# overall.net
KiCad netlist of a schematic drawn in Altium Designer
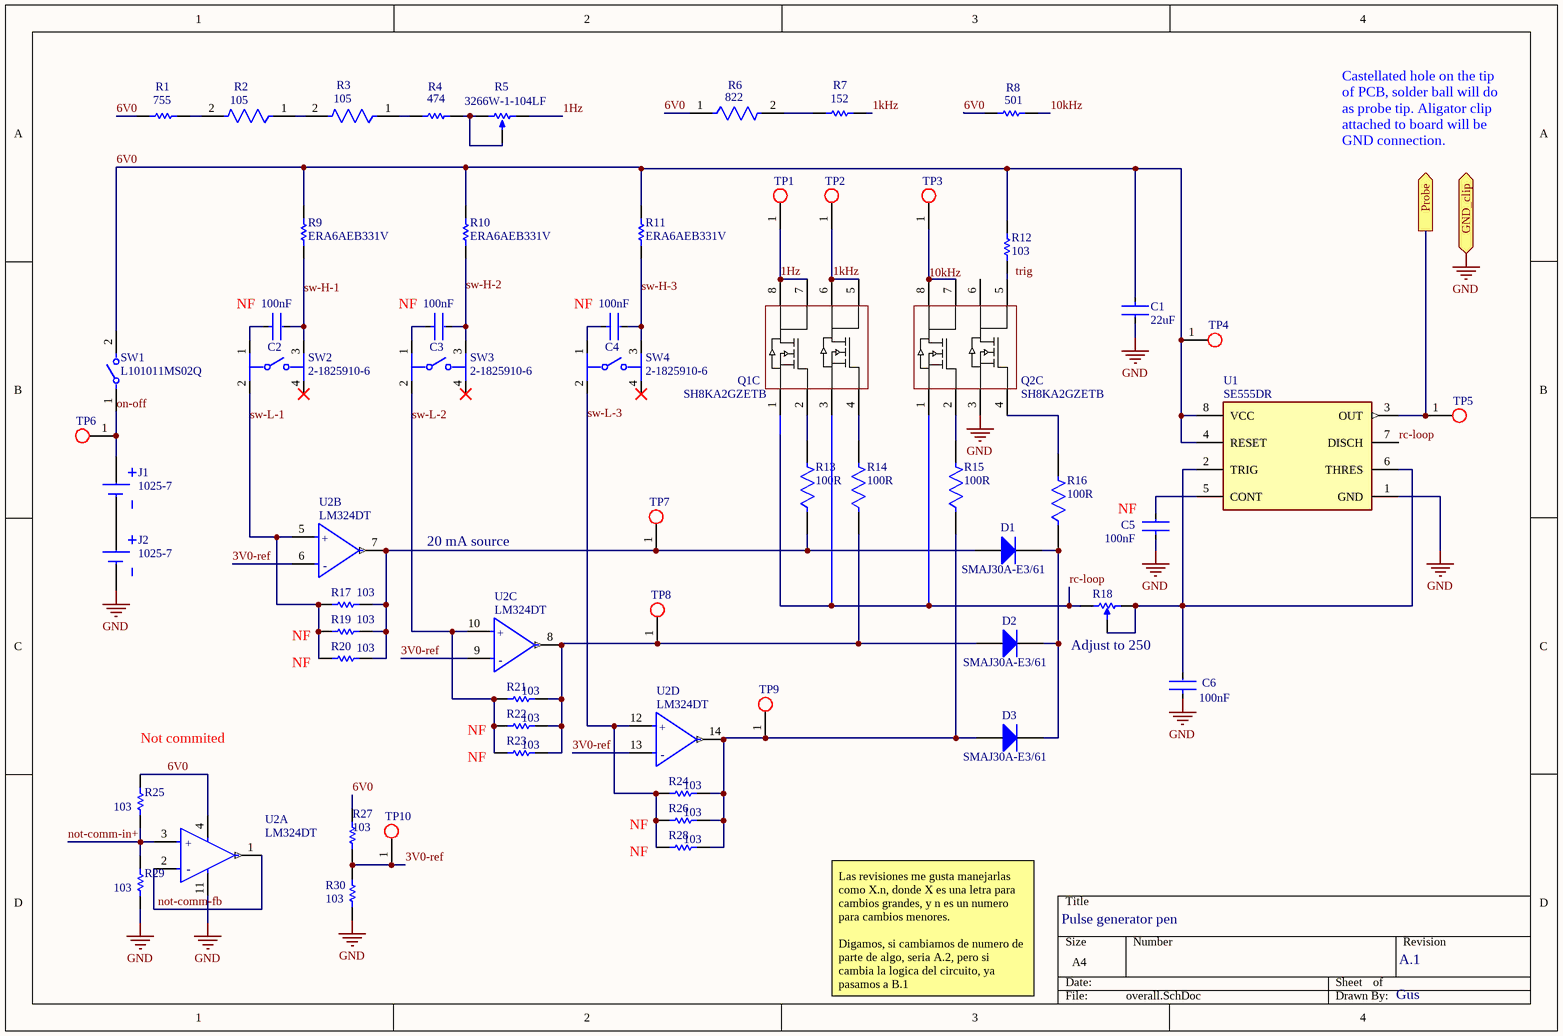
[diagram p0: overall.SchDoc]

(export (version "E")
  (design (tool "Eeschema 10.0.6"))
  (components
    (comp (ref "C1")
      (value "C2012X5R1V226M125AC")
      (footprint "FP-C2012-125-0_2-IPC_A")
      (description "Multilayer Ceramic Capacitors 22μF ±20% 35V X5R SMD 0805")
      (fields (field (name "TOLERANCE") "20%") (field (name "CAPACITANCE") "22uF"))
      (libsource (lib "Altium Content Vault") (part "b4654b650e69147ec39a6b967a45e02"))
    )
    (comp (ref "C2")
      (value "CL21B104KBCNNNC")
      (footprint "FP-CL21-IPC_A")
      (description "CL21 Series 0805 100nF 50V ±10% Tolerance X7R Multilayer Ceramic Chip Capacitor")
      (fields
        (field (name "TOLERANCE") "10%")
        (field (name "CAPACITANCE") "100nF")
        (field (name "VOLTAGE") "50V")
      )
      (libsource (lib "Altium Content Vault") (part "b4654b650e69147ec39a6b967a45e02"))
    )
    (comp (ref "C3")
      (value "CL21B104KBCNNNC")
      (footprint "FP-CL21-IPC_A")
      (description "CL21 Series 0805 100nF 50V ±10% Tolerance X7R Multilayer Ceramic Chip Capacitor")
      (fields
        (field (name "TOLERANCE") "10%")
        (field (name "CAPACITANCE") "100nF")
        (field (name "VOLTAGE") "50V")
      )
      (libsource (lib "Altium Content Vault") (part "b4654b650e69147ec39a6b967a45e02"))
    )
    (comp (ref "C4")
      (value "CL21B104KBCNNNC")
      (footprint "FP-CL21-IPC_A")
      (description "CL21 Series 0805 100nF 50V ±10% Tolerance X7R Multilayer Ceramic Chip Capacitor")
      (fields
        (field (name "TOLERANCE") "10%")
        (field (name "CAPACITANCE") "100nF")
        (field (name "VOLTAGE") "50V")
      )
      (libsource (lib "Altium Content Vault") (part "b4654b650e69147ec39a6b967a45e02"))
    )
    (comp (ref "C5")
      (value "CL21B104KBCNNNC")
      (footprint "FP-CL21-IPC_A")
      (description "CL21 Series 0805 100nF 50V ±10% Tolerance X7R Multilayer Ceramic Chip Capacitor")
      (fields
        (field (name "TOLERANCE") "10%")
        (field (name "CAPACITANCE") "100nF")
        (field (name "VOLTAGE") "50V")
      )
      (libsource (lib "Altium Content Vault") (part "b4654b650e69147ec39a6b967a45e02"))
    )
    (comp (ref "C6")
      (value "CL21B104KBCNNNC")
      (footprint "FP-CL21-IPC_A")
      (description "CL21 Series 0805 100nF 50V ±10% Tolerance X7R Multilayer Ceramic Chip Capacitor")
      (fields
        (field (name "TOLERANCE") "10%")
        (field (name "CAPACITANCE") "100nF")
        (field (name "VOLTAGE") "50V")
      )
      (libsource (lib "Altium Content Vault") (part "b4654b650e69147ec39a6b967a45e02"))
    )
    (comp (ref "D1")
      (value "SMAJ30A-E3/61")
      (footprint "VISH-DO-214AC-2_N")
      (fields (field (name "MANUFACTURER") "Vishay Semiconductor"))
      (libsource (lib "Altium Content Vault") (part "VISH-K1A2-2"))
    )
    (comp (ref "D2")
      (value "SMAJ30A-E3/61")
      (footprint "VISH-DO-214AC-2_N")
      (fields (field (name "MANUFACTURER") "Vishay Semiconductor"))
      (libsource (lib "Altium Content Vault") (part "VISH-K1A2-2"))
    )
    (comp (ref "D3")
      (value "SMAJ30A-E3/61")
      (footprint "VISH-DO-214AC-2_N")
      (fields (field (name "MANUFACTURER") "Vishay Semiconductor"))
      (libsource (lib "Altium Content Vault") (part "VISH-K1A2-2"))
    )
    (comp (ref "J1")
      (value "1025-7")
      (footprint "KEYSTONE-1025-7-2_V")
      (description "Holder for 2477 or 2430 Cells P/N 1025-7, Body 27.762 x 30.963 mm, THM")
      (fields (field (name "MANUFACTURER") "Keystone"))
      (libsource (lib "Altium Content Vault") (part "KEYSTONE-1025-7-2"))
    )
    (comp (ref "J2")
      (value "1025-7")
      (footprint "KEYSTONE-1025-7-2_V")
      (description "Holder for 2477 or 2430 Cells P/N 1025-7, Body 27.762 x 30.963 mm, THM")
      (fields (field (name "MANUFACTURER") "Keystone"))
      (libsource (lib "Altium Content Vault") (part "KEYSTONE-1025-7-2"))
    )
    (comp (ref "Q1")
      (value "SH8KA2GZETB")
      (footprint "SOIC127P600X175-8N")
      (libsource (lib "Cetys University") (part "SH8KA2GZETB"))
    )
    (comp (ref "Q2")
      (value "SH8KA2GZETB")
      (footprint "SOIC127P600X175-8N")
      (libsource (lib "Cetys University") (part "SH8KA2GZETB"))
    )
    (comp (ref "R1")
      (value "CRCW08057M50JNEA")
      (footprint "RESC2013X50X30LL20T20")
      (fields (field (name "MANUFACTURER") "Vishay Dale") (field (name "RESISTANCE") "755"))
      (libsource (lib "Altium Content Vault") (part "RES"))
    )
    (comp (ref "R2")
      (value "ERJ-6ENF1004V")
      (footprint "FP-ERJ6EN-IPC_A")
      (description "RES SMD 1M OHM 1% 1/8W 0805")
      (fields (field (name "RESISTANCE") "105") (field (name "TOLERANCE") "1%"))
      (libsource (lib "") (part "1029c3af85768c4190bb7ad29bc67b5_1"))
    )
    (comp (ref "R3")
      (value "ERJ-6ENF1004V")
      (footprint "FP-ERJ6EN-IPC_A")
      (description "RES SMD 1M OHM 1% 1/8W 0805")
      (fields (field (name "RESISTANCE") "105") (field (name "TOLERANCE") "1%"))
      (libsource (lib "") (part "1029c3af85768c4190bb7ad29bc67b5_1"))
    )
    (comp (ref "R4")
      (value "ERJ6ENF4703V")
      (footprint "RESC2013X70X40ML20T20")
      (fields (field (name "MANUFACTURER") "Panasonic") (field (name "RESISTANCE") "474"))
      (libsource (lib "Altium Content Vault") (part "RES"))
    )
    (comp (ref "R5")
      (value "3266W-1-104LF")
      (footprint "BOUR-3266W-3_V")
      (description "Square Trimpot Trimming Potentiometer, 100 KOhm, 0.25 W, -55 to 125 degC, 3-Pin THD, RoHS, Tube")
      (fields (field (name "TOLERANCE") "+/-10%") (field (name "MANUFACTURER") "Bourns"))
      (libsource (lib "Altium Content Vault") (part "BOUR-POT-3"))
    )
    (comp (ref "R6")
      (value "RC2012J822CS")
      (footprint "FP-RC2012-IPC_A")
      (description "Res Thick Film 0805 8.2kΩ 5% 0.125W ±100ppm/°C Molded SMD T/R")
      (fields (field (name "RESISTANCE") "822") (field (name "TOLERANCE") "5%"))
      (libsource (lib "") (part "1029c3af85768c4190bb7ad29bc67b5_1"))
    )
    (comp (ref "R7")
      (value "RC0805FR-071K5L")
      (footprint "RESC2013X60X35LL10T20")
      (description "RES 1.50K OHM 1/8W 1% 0805 SMD")
      (fields (field (name "MANUFACTURER") "Yageo") (field (name "RESISTANCE") "152"))
      (libsource (lib "") (part "RES-2_1"))
    )
    (comp (ref "R8")
      (value "WSLP0805R0500FEA")
      (footprint "RESC2013X58X38LL25T25")
      (fields (field (name "MANUFACTURER") "Vishay Dale") (field (name "RESISTANCE") "501"))
      (libsource (lib "Altium Content Vault") (part "RES"))
    )
    (comp (ref "R9")
      (value "ERA6AEB331V")
      (footprint "RESC2013X60X40LL20T25")
      (fields (field (name "MANUFACTURER") "Panasonic"))
      (libsource (lib "Altium Content Vault") (part "RES"))
    )
    (comp (ref "R10")
      (value "ERA6AEB331V")
      (footprint "RESC2013X60X40LL20T25")
      (fields (field (name "MANUFACTURER") "Panasonic"))
      (libsource (lib "Altium Content Vault") (part "RES"))
    )
    (comp (ref "R11")
      (value "ERA6AEB331V")
      (footprint "RESC2013X60X40LL20T25")
      (fields (field (name "MANUFACTURER") "Panasonic"))
      (libsource (lib "Altium Content Vault") (part "RES"))
    )
    (comp (ref "R12")
      (value "RC0805FR-0710KL")
      (footprint "RESC2013X60X35NL10T20")
      (description "Chip Resistor, 10 KOhm, +/- 1%, 0.125 W, -55 to 155 degC, 0805 (2012 Metric), RoHS, Tape and Reel")
      (fields (field (name "MANUFACTURER") "Yageo") (field (name "RESISTANCE") "103"))
      (libsource (lib "Altium Content Vault") (part "RES-2"))
    )
    (comp (ref "R13")
      (value "CRCW0805100RFKEAHP")
      (footprint "FP-CRCW0805-HPe3-IPC_A")
      (description "RES Thick Film, 100Ω, 1%, 0.5W, 100ppm/°C, 0805")
      (fields (field (name "TOLERANCE") "1%") (field (name "RESISTANCE") "100R"))
      (libsource (lib "Altium Content Vault") (part "1029c3af85768c4190bb7ad29bc67b5"))
    )
    (comp (ref "R14")
      (value "CRCW0805100RFKEAHP")
      (footprint "FP-CRCW0805-HPe3-IPC_A")
      (description "RES Thick Film, 100Ω, 1%, 0.5W, 100ppm/°C, 0805")
      (fields (field (name "TOLERANCE") "1%") (field (name "RESISTANCE") "100R"))
      (libsource (lib "Altium Content Vault") (part "1029c3af85768c4190bb7ad29bc67b5"))
    )
    (comp (ref "R15")
      (value "CRCW0805100RFKEAHP")
      (footprint "FP-CRCW0805-HPe3-IPC_A")
      (description "RES Thick Film, 100Ω, 1%, 0.5W, 100ppm/°C, 0805")
      (fields (field (name "TOLERANCE") "1%") (field (name "RESISTANCE") "100R"))
      (libsource (lib "Altium Content Vault") (part "1029c3af85768c4190bb7ad29bc67b5"))
    )
    (comp (ref "R16")
      (value "CRCW0805100RFKEAHP")
      (footprint "FP-CRCW0805-HPe3-IPC_A")
      (description "RES Thick Film, 100Ω, 1%, 0.5W, 100ppm/°C, 0805")
      (fields (field (name "TOLERANCE") "1%") (field (name "RESISTANCE") "100R"))
      (libsource (lib "Altium Content Vault") (part "1029c3af85768c4190bb7ad29bc67b5"))
    )
    (comp (ref "R17")
      (value "RC0805FR-0710KL")
      (footprint "RESC2013X60X35NL10T20")
      (description "Chip Resistor, 10 KOhm, +/- 1%, 0.125 W, -55 to 155 degC, 0805 (2012 Metric), RoHS, Tape and Reel")
      (fields (field (name "MANUFACTURER") "Yageo") (field (name "RESISTANCE") "103"))
      (libsource (lib "Altium Content Vault") (part "RES-2"))
    )
    (comp (ref "R18")
      (value "3296W-1-102LF")
      (footprint "BOUR-3296W-1-3")
      (description "Square Trimpot(R) Trimming Potentiometer, 1000 Ohm, -55 to 125 degC, 3-Pin THD, RoHS, Tube")
      (fields (field (name "TOLERANCE") "1%"))
      (libsource (lib "Altium Content Vault") (part "RES-ADJ-3"))
    )
    (comp (ref "R19")
      (value "RC0805FR-0710KL")
      (footprint "RESC2013X60X35NL10T20")
      (description "Chip Resistor, 10 KOhm, +/- 1%, 0.125 W, -55 to 155 degC, 0805 (2012 Metric), RoHS, Tape and Reel")
      (fields (field (name "MANUFACTURER") "Yageo") (field (name "RESISTANCE") "103"))
      (libsource (lib "Altium Content Vault") (part "RES-2"))
    )
    (comp (ref "R20")
      (value "RC0805FR-0710KL")
      (footprint "RESC2013X60X35NL10T20")
      (description "Chip Resistor, 10 KOhm, +/- 1%, 0.125 W, -55 to 155 degC, 0805 (2012 Metric), RoHS, Tape and Reel")
      (fields (field (name "MANUFACTURER") "Yageo") (field (name "RESISTANCE") "103"))
      (libsource (lib "Altium Content Vault") (part "RES-2"))
    )
    (comp (ref "R21")
      (value "RC0805FR-0710KL")
      (footprint "RESC2013X60X35NL10T20")
      (description "Chip Resistor, 10 KOhm, +/- 1%, 0.125 W, -55 to 155 degC, 0805 (2012 Metric), RoHS, Tape and Reel")
      (fields (field (name "MANUFACTURER") "Yageo") (field (name "RESISTANCE") "103"))
      (libsource (lib "Altium Content Vault") (part "RES-2"))
    )
    (comp (ref "R22")
      (value "RC0805FR-0710KL")
      (footprint "RESC2013X60X35NL10T20")
      (description "Chip Resistor, 10 KOhm, +/- 1%, 0.125 W, -55 to 155 degC, 0805 (2012 Metric), RoHS, Tape and Reel")
      (fields (field (name "MANUFACTURER") "Yageo") (field (name "RESISTANCE") "103"))
      (libsource (lib "Altium Content Vault") (part "RES-2"))
    )
    (comp (ref "R23")
      (value "RC0805FR-0710KL")
      (footprint "RESC2013X60X35NL10T20")
      (description "Chip Resistor, 10 KOhm, +/- 1%, 0.125 W, -55 to 155 degC, 0805 (2012 Metric), RoHS, Tape and Reel")
      (fields (field (name "MANUFACTURER") "Yageo") (field (name "RESISTANCE") "103"))
      (libsource (lib "Altium Content Vault") (part "RES-2"))
    )
    (comp (ref "R24")
      (value "RC0805FR-0710KL")
      (footprint "RESC2013X60X35NL10T20")
      (description "Chip Resistor, 10 KOhm, +/- 1%, 0.125 W, -55 to 155 degC, 0805 (2012 Metric), RoHS, Tape and Reel")
      (fields (field (name "MANUFACTURER") "Yageo") (field (name "RESISTANCE") "103"))
      (libsource (lib "Altium Content Vault") (part "RES-2"))
    )
    (comp (ref "R25")
      (value "RC0805FR-0710KL")
      (footprint "RESC2013X60X35NL10T20")
      (description "Chip Resistor, 10 KOhm, +/- 1%, 0.125 W, -55 to 155 degC, 0805 (2012 Metric), RoHS, Tape and Reel")
      (fields (field (name "MANUFACTURER") "Yageo") (field (name "RESISTANCE") "103"))
      (libsource (lib "Altium Content Vault") (part "RES-2"))
    )
    (comp (ref "R26")
      (value "RC0805FR-0710KL")
      (footprint "RESC2013X60X35NL10T20")
      (description "Chip Resistor, 10 KOhm, +/- 1%, 0.125 W, -55 to 155 degC, 0805 (2012 Metric), RoHS, Tape and Reel")
      (fields (field (name "MANUFACTURER") "Yageo") (field (name "RESISTANCE") "103"))
      (libsource (lib "Altium Content Vault") (part "RES-2"))
    )
    (comp (ref "R27")
      (value "RC0805FR-0710KL")
      (footprint "RESC2013X60X35NL10T20")
      (description "Chip Resistor, 10 KOhm, +/- 1%, 0.125 W, -55 to 155 degC, 0805 (2012 Metric), RoHS, Tape and Reel")
      (fields (field (name "MANUFACTURER") "Yageo") (field (name "RESISTANCE") "103"))
      (libsource (lib "Altium Content Vault") (part "RES-2"))
    )
    (comp (ref "R28")
      (value "RC0805FR-0710KL")
      (footprint "RESC2013X60X35NL10T20")
      (description "Chip Resistor, 10 KOhm, +/- 1%, 0.125 W, -55 to 155 degC, 0805 (2012 Metric), RoHS, Tape and Reel")
      (fields (field (name "MANUFACTURER") "Yageo") (field (name "RESISTANCE") "103"))
      (libsource (lib "Altium Content Vault") (part "RES-2"))
    )
    (comp (ref "R29")
      (value "RC0805FR-0710KL")
      (footprint "RESC2013X60X35NL10T20")
      (description "Chip Resistor, 10 KOhm, +/- 1%, 0.125 W, -55 to 155 degC, 0805 (2012 Metric), RoHS, Tape and Reel")
      (fields (field (name "MANUFACTURER") "Yageo") (field (name "RESISTANCE") "103"))
      (libsource (lib "Altium Content Vault") (part "RES-2"))
    )
    (comp (ref "R30")
      (value "RC0805FR-0710KL")
      (footprint "RESC2013X60X35NL10T20")
      (description "Chip Resistor, 10 KOhm, +/- 1%, 0.125 W, -55 to 155 degC, 0805 (2012 Metric), RoHS, Tape and Reel")
      (fields (field (name "MANUFACTURER") "Yageo") (field (name "RESISTANCE") "103"))
      (libsource (lib "Altium Content Vault") (part "RES-2"))
    )
    (comp (ref "SW1")
      (value "L101011MS02Q")
      (footprint "FP-L101011MS02Q-MFG")
      (description "SWITCH SLIDE SPST 4A 125V")
      (libsource (lib "Altium Content Vault") (part "bb27bde45df87f1f469753f287ef5ae"))
    )
    (comp (ref "SW2")
      (value "2-1825910-6")
      (footprint "FP-2-1825910-6-MFG")
      (description "SWITCH TACTILE SPST-NO 0.05A 24V")
      (libsource (lib "Altium Content Vault") (part "b8895f3f4cefb76e1819d2863dba89b"))
    )
    (comp (ref "SW3")
      (value "2-1825910-6")
      (footprint "FP-2-1825910-6-MFG")
      (description "SWITCH TACTILE SPST-NO 0.05A 24V")
      (libsource (lib "Altium Content Vault") (part "b8895f3f4cefb76e1819d2863dba89b"))
    )
    (comp (ref "SW4")
      (value "2-1825910-6")
      (footprint "FP-2-1825910-6-MFG")
      (description "SWITCH TACTILE SPST-NO 0.05A 24V")
      (libsource (lib "Altium Content Vault") (part "b8895f3f4cefb76e1819d2863dba89b"))
    )
    (comp (ref "TP1")
      (value "TP_opening")
      (footprint "New footprint 1")
      (description "Soldermask opening or top layer pad for testing purposes")
      (libsource (lib "Cetys University") (part "TP1"))
    )
    (comp (ref "TP2")
      (value "TP_opening")
      (footprint "New footprint 1")
      (description "Soldermask opening or top layer pad for testing purposes")
      (libsource (lib "Cetys University") (part "TP1"))
    )
    (comp (ref "TP3")
      (value "TP_opening")
      (footprint "New footprint 1")
      (description "Soldermask opening or top layer pad for testing purposes")
      (libsource (lib "Cetys University") (part "TP1"))
    )
    (comp (ref "TP4")
      (value "TP_opening")
      (footprint "New footprint 1")
      (description "Soldermask opening or top layer pad for testing purposes")
      (libsource (lib "Cetys University") (part "TP1"))
    )
    (comp (ref "TP5")
      (value "TP_opening")
      (footprint "New footprint 1")
      (description "Soldermask opening or top layer pad for testing purposes")
      (libsource (lib "Cetys University") (part "TP1"))
    )
    (comp (ref "TP6")
      (value "TP_opening")
      (footprint "New footprint 1")
      (description "Soldermask opening or top layer pad for testing purposes")
      (libsource (lib "Cetys University") (part "TP1"))
    )
    (comp (ref "TP7")
      (value "TP_opening")
      (footprint "New footprint 1")
      (description "Soldermask opening or top layer pad for testing purposes")
      (libsource (lib "Cetys University") (part "TP1"))
    )
    (comp (ref "TP8")
      (value "TP_opening")
      (footprint "New footprint 1")
      (description "Soldermask opening or top layer pad for testing purposes")
      (libsource (lib "Cetys University") (part "TP1"))
    )
    (comp (ref "TP9")
      (value "TP_opening")
      (footprint "New footprint 1")
      (description "Soldermask opening or top layer pad for testing purposes")
      (libsource (lib "Cetys University") (part "TP1"))
    )
    (comp (ref "TP10")
      (value "TP_opening")
      (footprint "New footprint 1")
      (description "Soldermask opening or top layer pad for testing purposes")
      (libsource (lib "Cetys University") (part "TP1"))
    )
    (comp (ref "U1")
      (value "SE555DR")
      (footprint "FP-D0008A-MFG")
      (description "IC OSC SGL TIMER 100KHZ 8-SOIC")
      (libsource (lib "Altium Content Vault") (part "dd5b8434f2346953fd8290325fbf3de"))
    )
    (comp (ref "U2")
      (value "LM324DT")
      (footprint "FP-SO-14-MFG")
      (description "IC OPAMP GP 4 CIRCUIT 14SO")
      (fields
        (field (name "OCTOPART") "https://octopart.com/lm324dt-stmicroelectronics-39579146")
        (field (name "MANUFACTURER") "STMicroelectronics")
      )
      (libsource (lib "Altium Content Vault") (part "a065ef67e5aa9ef3942d43d6008d043"))
    )
  )
  (nets
    (net (code "1") (name "/1Hz") (class "Default")
      (node (ref "Q1") (pin "7") (pinfunction "7_7") (pintype "passive"))
      (node (ref "Q1") (pin "8") (pinfunction "8_8") (pintype "passive"))
      (node (ref "R5") (pin "3") (pinfunction "CW_3") (pintype "passive"))
      (node (ref "TP1") (pin "1") (pinfunction "1_1") (pintype "passive"))
    )
    (net (code "2") (name "/1kHz") (class "Default")
      (node (ref "Q1") (pin "5") (pinfunction "5_5") (pintype "passive"))
      (node (ref "Q1") (pin "6") (pinfunction "6_6") (pintype "passive"))
      (node (ref "R7") (pin "2") (pinfunction "2_2") (pintype "passive"))
      (node (ref "TP2") (pin "1") (pinfunction "1_1") (pintype "passive"))
    )
    (net (code "3") (name "/3V0-ref") (class "Default")
      (node (ref "R27") (pin "1") (pinfunction "1_1") (pintype "passive"))
      (node (ref "R30") (pin "2") (pinfunction "2_2") (pintype "passive"))
      (node (ref "TP10") (pin "1") (pinfunction "1_1") (pintype "passive"))
      (node (ref "U2") (pin "13") (pinfunction "Inverting_Input_4_13") (pintype "tri_state"))
      (node (ref "U2") (pin "6") (pinfunction "Inverting_Input_2_6") (pintype "tri_state"))
      (node (ref "U2") (pin "9") (pinfunction "Inverting_Input_3_9") (pintype "tri_state"))
    )
    (net (code "4") (name "/6V0") (class "Default")
      (node (ref "C1") (pin "1") (pinfunction "1_1") (pintype "passive"))
      (node (ref "R1") (pin "2") (pinfunction "2_2") (pintype "passive"))
      (node (ref "R10") (pin "1") (pinfunction "1_1") (pintype "passive"))
      (node (ref "R11") (pin "1") (pinfunction "1_1") (pintype "passive"))
      (node (ref "R12") (pin "1") (pinfunction "1_1") (pintype "passive"))
      (node (ref "R25") (pin "2") (pinfunction "2_2") (pintype "passive"))
      (node (ref "R27") (pin "2") (pinfunction "2_2") (pintype "passive"))
      (node (ref "R6") (pin "1") (pinfunction "1_1") (pintype "passive"))
      (node (ref "R8") (pin "1") (pinfunction "1_1") (pintype "passive"))
      (node (ref "R9") (pin "1") (pinfunction "1_1") (pintype "passive"))
      (node (ref "SW1") (pin "2") (pinfunction "2_2") (pintype "passive"))
      (node (ref "TP4") (pin "1") (pinfunction "1_1") (pintype "passive"))
      (node (ref "U1") (pin "4") (pinfunction "RESET_4") (pintype "passive"))
      (node (ref "U1") (pin "8") (pinfunction "VCC_8") (pintype "power_in"))
      (node (ref "U2") (pin "4") (pinfunction "VCC+_4") (pintype "power_in"))
    )
    (net (code "5") (name "/10kHz") (class "Default")
      (node (ref "Q2") (pin "7") (pinfunction "7_7") (pintype "passive"))
      (node (ref "Q2") (pin "8") (pinfunction "8_8") (pintype "passive"))
      (node (ref "R8") (pin "2") (pinfunction "2_2") (pintype "passive"))
      (node (ref "TP3") (pin "1") (pinfunction "1_1") (pintype "passive"))
    )
    (net (code "6") (name "/Probe") (class "Default")
      (node (ref "TP5") (pin "1") (pinfunction "1_1") (pintype "passive"))
      (node (ref "U1") (pin "3") (pinfunction "OUT_3") (pintype "output"))
    )
    (net (code "7") (name "/not-comm-fb") (class "Default")
      (node (ref "U2") (pin "1") (pinfunction "Output_1_1") (pintype "output"))
      (node (ref "U2") (pin "2") (pinfunction "Inverting_Input_1_2") (pintype "tri_state"))
    )
    (net (code "8") (name "/not-comm-in+") (class "Default")
      (node (ref "R25") (pin "1") (pinfunction "1_1") (pintype "passive"))
      (node (ref "R29") (pin "2") (pinfunction "2_2") (pintype "passive"))
      (node (ref "U2") (pin "3") (pinfunction "Non-Inverting_Input_1_3") (pintype "tri_state"))
    )
    (net (code "9") (name "/on-off") (class "Default")
      (node (ref "J1") (pin "1") (pinfunction "+_1") (pintype "passive"))
      (node (ref "SW1") (pin "1") (pinfunction "1_1") (pintype "passive"))
      (node (ref "TP6") (pin "1") (pinfunction "1_1") (pintype "passive"))
    )
    (net (code "10") (name "/rc-loop") (class "Default")
      (node (ref "Q1") (pin "1") (pinfunction "1_1") (pintype "passive"))
      (node (ref "Q1") (pin "3") (pinfunction "3_3") (pintype "passive"))
      (node (ref "Q2") (pin "1") (pinfunction "1_1") (pintype "passive"))
      (node (ref "R18") (pin "1") (pinfunction "A_1") (pintype "passive"))
      (node (ref "U1") (pin "7") (pinfunction "DISCH_7") (pintype "passive"))
    )
    (net (code "11") (name "/sw-H-1") (class "Default")
      (node (ref "C2") (pin "2") (pinfunction "2_2") (pintype "passive"))
      (node (ref "R9") (pin "2") (pinfunction "2_2") (pintype "passive"))
      (node (ref "SW2") (pin "3") (pinfunction "3_3") (pintype "passive"))
    )
    (net (code "12") (name "/sw-H-2") (class "Default")
      (node (ref "C3") (pin "2") (pinfunction "2_2") (pintype "passive"))
      (node (ref "R10") (pin "2") (pinfunction "2_2") (pintype "passive"))
      (node (ref "SW3") (pin "3") (pinfunction "3_3") (pintype "passive"))
    )
    (net (code "13") (name "/sw-H-3") (class "Default")
      (node (ref "C4") (pin "2") (pinfunction "2_2") (pintype "passive"))
      (node (ref "R11") (pin "2") (pinfunction "2_2") (pintype "passive"))
      (node (ref "SW4") (pin "3") (pinfunction "3_3") (pintype "passive"))
    )
    (net (code "14") (name "/sw-L-1") (class "Default")
      (node (ref "R17") (pin "2") (pinfunction "2_2") (pintype "passive"))
      (node (ref "R19") (pin "2") (pinfunction "2_2") (pintype "passive"))
      (node (ref "R20") (pin "2") (pinfunction "2_2") (pintype "passive"))
      (node (ref "SW2") (pin "2") (pinfunction "2_2") (pintype "passive"))
      (node (ref "U2") (pin "5") (pinfunction "Non-Inverting_Input_2_5") (pintype "tri_state"))
    )
    (net (code "15") (name "/sw-L-2") (class "Default")
      (node (ref "R21") (pin "2") (pinfunction "2_2") (pintype "passive"))
      (node (ref "R22") (pin "2") (pinfunction "2_2") (pintype "passive"))
      (node (ref "R23") (pin "2") (pinfunction "2_2") (pintype "passive"))
      (node (ref "SW3") (pin "2") (pinfunction "2_2") (pintype "passive"))
      (node (ref "U2") (pin "10") (pinfunction "Non-Inverting_Input_3_10") (pintype "tri_state"))
    )
    (net (code "16") (name "/sw-L-3") (class "Default")
      (node (ref "R24") (pin "2") (pinfunction "2_2") (pintype "passive"))
      (node (ref "R26") (pin "2") (pinfunction "2_2") (pintype "passive"))
      (node (ref "R28") (pin "2") (pinfunction "2_2") (pintype "passive"))
      (node (ref "SW4") (pin "2") (pinfunction "2_2") (pintype "passive"))
      (node (ref "U2") (pin "12") (pinfunction "Non-Inverting_Input_4_12") (pintype "tri_state"))
    )
    (net (code "18") (name "GND") (class "Default")
      (node (ref "C1") (pin "2") (pinfunction "2_2") (pintype "passive"))
      (node (ref "C5") (pin "1") (pinfunction "1_1") (pintype "passive"))
      (node (ref "C6") (pin "1") (pinfunction "1_1") (pintype "passive"))
      (node (ref "J2") (pin "2") (pinfunction "-_2") (pintype "passive"))
      (node (ref "Q2") (pin "3") (pinfunction "3_3") (pintype "passive"))
      (node (ref "R29") (pin "1") (pinfunction "1_1") (pintype "passive"))
      (node (ref "R30") (pin "1") (pinfunction "1_1") (pintype "passive"))
      (node (ref "U1") (pin "1") (pinfunction "GND_1") (pintype "power_in"))
      (node (ref "U2") (pin "11") (pinfunction "VCC-_11") (pintype "power_in"))
    )
    (net (code "19") (name "Net-(C2-Pad1)") (class "Default")
      (node (ref "C2") (pin "1") (pinfunction "1_1") (pintype "passive"))
      (node (ref "SW2") (pin "1") (pinfunction "1_1") (pintype "passive"))
    )
    (net (code "20") (name "Net-(C3-Pad1)") (class "Default")
      (node (ref "C3") (pin "1") (pinfunction "1_1") (pintype "passive"))
      (node (ref "SW3") (pin "1") (pinfunction "1_1") (pintype "passive"))
    )
    (net (code "21") (name "Net-(C4-Pad1)") (class "Default")
      (node (ref "C4") (pin "1") (pinfunction "1_1") (pintype "passive"))
      (node (ref "SW4") (pin "1") (pinfunction "1_1") (pintype "passive"))
    )
    (net (code "22") (name "Net-(D1-A)") (class "Default")
      (node (ref "D1") (pin "2") (pinfunction "A_2") (pintype "passive"))
      (node (ref "R13") (pin "1") (pinfunction "1_1") (pintype "passive"))
      (node (ref "R17") (pin "1") (pinfunction "1_1") (pintype "passive"))
      (node (ref "R19") (pin "1") (pinfunction "1_1") (pintype "passive"))
      (node (ref "R20") (pin "1") (pinfunction "1_1") (pintype "passive"))
      (node (ref "TP7") (pin "1") (pinfunction "1_1") (pintype "passive"))
      (node (ref "U2") (pin "7") (pinfunction "Output_2_7") (pintype "output"))
    )
    (net (code "23") (name "Net-(D1-K)") (class "Default")
      (node (ref "D1") (pin "1") (pinfunction "K_1") (pintype "passive"))
      (node (ref "D2") (pin "1") (pinfunction "K_1") (pintype "passive"))
      (node (ref "D3") (pin "1") (pinfunction "K_1") (pintype "passive"))
      (node (ref "R16") (pin "1") (pinfunction "1_1") (pintype "passive"))
    )
    (net (code "24") (name "Net-(D2-A)") (class "Default")
      (node (ref "D2") (pin "2") (pinfunction "A_2") (pintype "passive"))
      (node (ref "R14") (pin "1") (pinfunction "1_1") (pintype "passive"))
      (node (ref "R21") (pin "1") (pinfunction "1_1") (pintype "passive"))
      (node (ref "R22") (pin "1") (pinfunction "1_1") (pintype "passive"))
      (node (ref "R23") (pin "1") (pinfunction "1_1") (pintype "passive"))
      (node (ref "TP8") (pin "1") (pinfunction "1_1") (pintype "passive"))
      (node (ref "U2") (pin "8") (pinfunction "Output_3_8") (pintype "output"))
    )
    (net (code "25") (name "Net-(D3-A)") (class "Default")
      (node (ref "D3") (pin "2") (pinfunction "A_2") (pintype "passive"))
      (node (ref "R15") (pin "1") (pinfunction "1_1") (pintype "passive"))
      (node (ref "R24") (pin "1") (pinfunction "1_1") (pintype "passive"))
      (node (ref "R26") (pin "1") (pinfunction "1_1") (pintype "passive"))
      (node (ref "R28") (pin "1") (pinfunction "1_1") (pintype "passive"))
      (node (ref "TP9") (pin "1") (pinfunction "1_1") (pintype "passive"))
      (node (ref "U2") (pin "14") (pinfunction "Output_4_14") (pintype "output"))
    )
    (net (code "26") (name "Net-(J1--)") (class "Default")
      (node (ref "J1") (pin "2") (pinfunction "-_2") (pintype "passive"))
      (node (ref "J2") (pin "1") (pinfunction "+_1") (pintype "passive"))
    )
    (net (code "27") (name "Net-(Q1-Pad2)") (class "Default")
      (node (ref "Q1") (pin "2") (pinfunction "2_2") (pintype "passive"))
      (node (ref "R13") (pin "2") (pinfunction "2_2") (pintype "passive"))
    )
    (net (code "28") (name "Net-(Q1-Pad4)") (class "Default")
      (node (ref "Q1") (pin "4") (pinfunction "4_4") (pintype "passive"))
      (node (ref "R14") (pin "2") (pinfunction "2_2") (pintype "passive"))
    )
    (net (code "29") (name "Net-(Q2-Pad2)") (class "Default")
      (node (ref "Q2") (pin "2") (pinfunction "2_2") (pintype "passive"))
      (node (ref "R15") (pin "2") (pinfunction "2_2") (pintype "passive"))
    )
    (net (code "30") (name "Net-(Q2-Pad4)") (class "Default")
      (node (ref "Q2") (pin "4") (pinfunction "4_4") (pintype "passive"))
      (node (ref "R16") (pin "2") (pinfunction "2_2") (pintype "passive"))
    )
    (net (code "31") (name "Net-(Q2-Pad5)") (class "Default")
      (node (ref "Q2") (pin "5") (pinfunction "5_5") (pintype "passive"))
      (node (ref "R12") (pin "2") (pinfunction "2_2") (pintype "passive"))
    )
    (net (code "32") (name "Net-(R1-Pad1)") (class "Default")
      (node (ref "R1") (pin "1") (pinfunction "1_1") (pintype "passive"))
      (node (ref "R2") (pin "2") (pinfunction "2_2") (pintype "passive"))
    )
    (net (code "33") (name "Net-(R2-Pad1)") (class "Default")
      (node (ref "R2") (pin "1") (pinfunction "1_1") (pintype "passive"))
      (node (ref "R3") (pin "2") (pinfunction "2_2") (pintype "passive"))
    )
    (net (code "34") (name "Net-(R3-Pad1)") (class "Default")
      (node (ref "R3") (pin "1") (pinfunction "1_1") (pintype "passive"))
      (node (ref "R4") (pin "1") (pinfunction "1_1") (pintype "passive"))
    )
    (net (code "35") (name "Net-(R5-CCW)") (class "Default")
      (node (ref "R4") (pin "2") (pinfunction "2_2") (pintype "passive"))
      (node (ref "R5") (pin "1") (pinfunction "CCW_1") (pintype "passive"))
      (node (ref "R5") (pin "2") (pinfunction "WIPER_2") (pintype "passive"))
    )
    (net (code "36") (name "Net-(R6-Pad2)") (class "Default")
      (node (ref "R6") (pin "2") (pinfunction "2_2") (pintype "passive"))
      (node (ref "R7") (pin "1") (pinfunction "1_1") (pintype "passive"))
    )
    (net (code "37") (name "Net-(R18-B)") (class "Default")
      (node (ref "C6") (pin "2") (pinfunction "2_2") (pintype "passive"))
      (node (ref "R18") (pin "2") (pinfunction "B_2") (pintype "passive"))
      (node (ref "R18") (pin "3") (pinfunction "TAP_3") (pintype "passive"))
      (node (ref "U1") (pin "2") (pinfunction "TRIG_2") (pintype "passive"))
      (node (ref "U1") (pin "6") (pinfunction "THRES_6") (pintype "passive"))
    )
    (net (code "38") (name "Net-(U1-CONT)") (class "Default")
      (node (ref "C5") (pin "2") (pinfunction "2_2") (pintype "passive"))
      (node (ref "U1") (pin "5") (pinfunction "CONT_5") (pintype "passive"))
    )
    (net (code "39") (name "unconnected-(Q2-Pad6)") (class "Default")
      (node (ref "Q2") (pin "6") (pinfunction "6_6") (pintype "passive"))
    )
    (net (code "40") (name "unconnected-(SW2-Pad4)") (class "Default")
      (node (ref "SW2") (pin "4") (pinfunction "4_4") (pintype "passive+no_connect"))
    )
    (net (code "41") (name "unconnected-(SW3-Pad4)") (class "Default")
      (node (ref "SW3") (pin "4") (pinfunction "4_4") (pintype "passive+no_connect"))
    )
    (net (code "42") (name "unconnected-(SW4-Pad4)") (class "Default")
      (node (ref "SW4") (pin "4") (pinfunction "4_4") (pintype "passive+no_connect"))
    )
  )
)
